# SCH_stm-mainboard_2026-06-05.net
KiCad netlist of a schematic drawn in EasyEDA
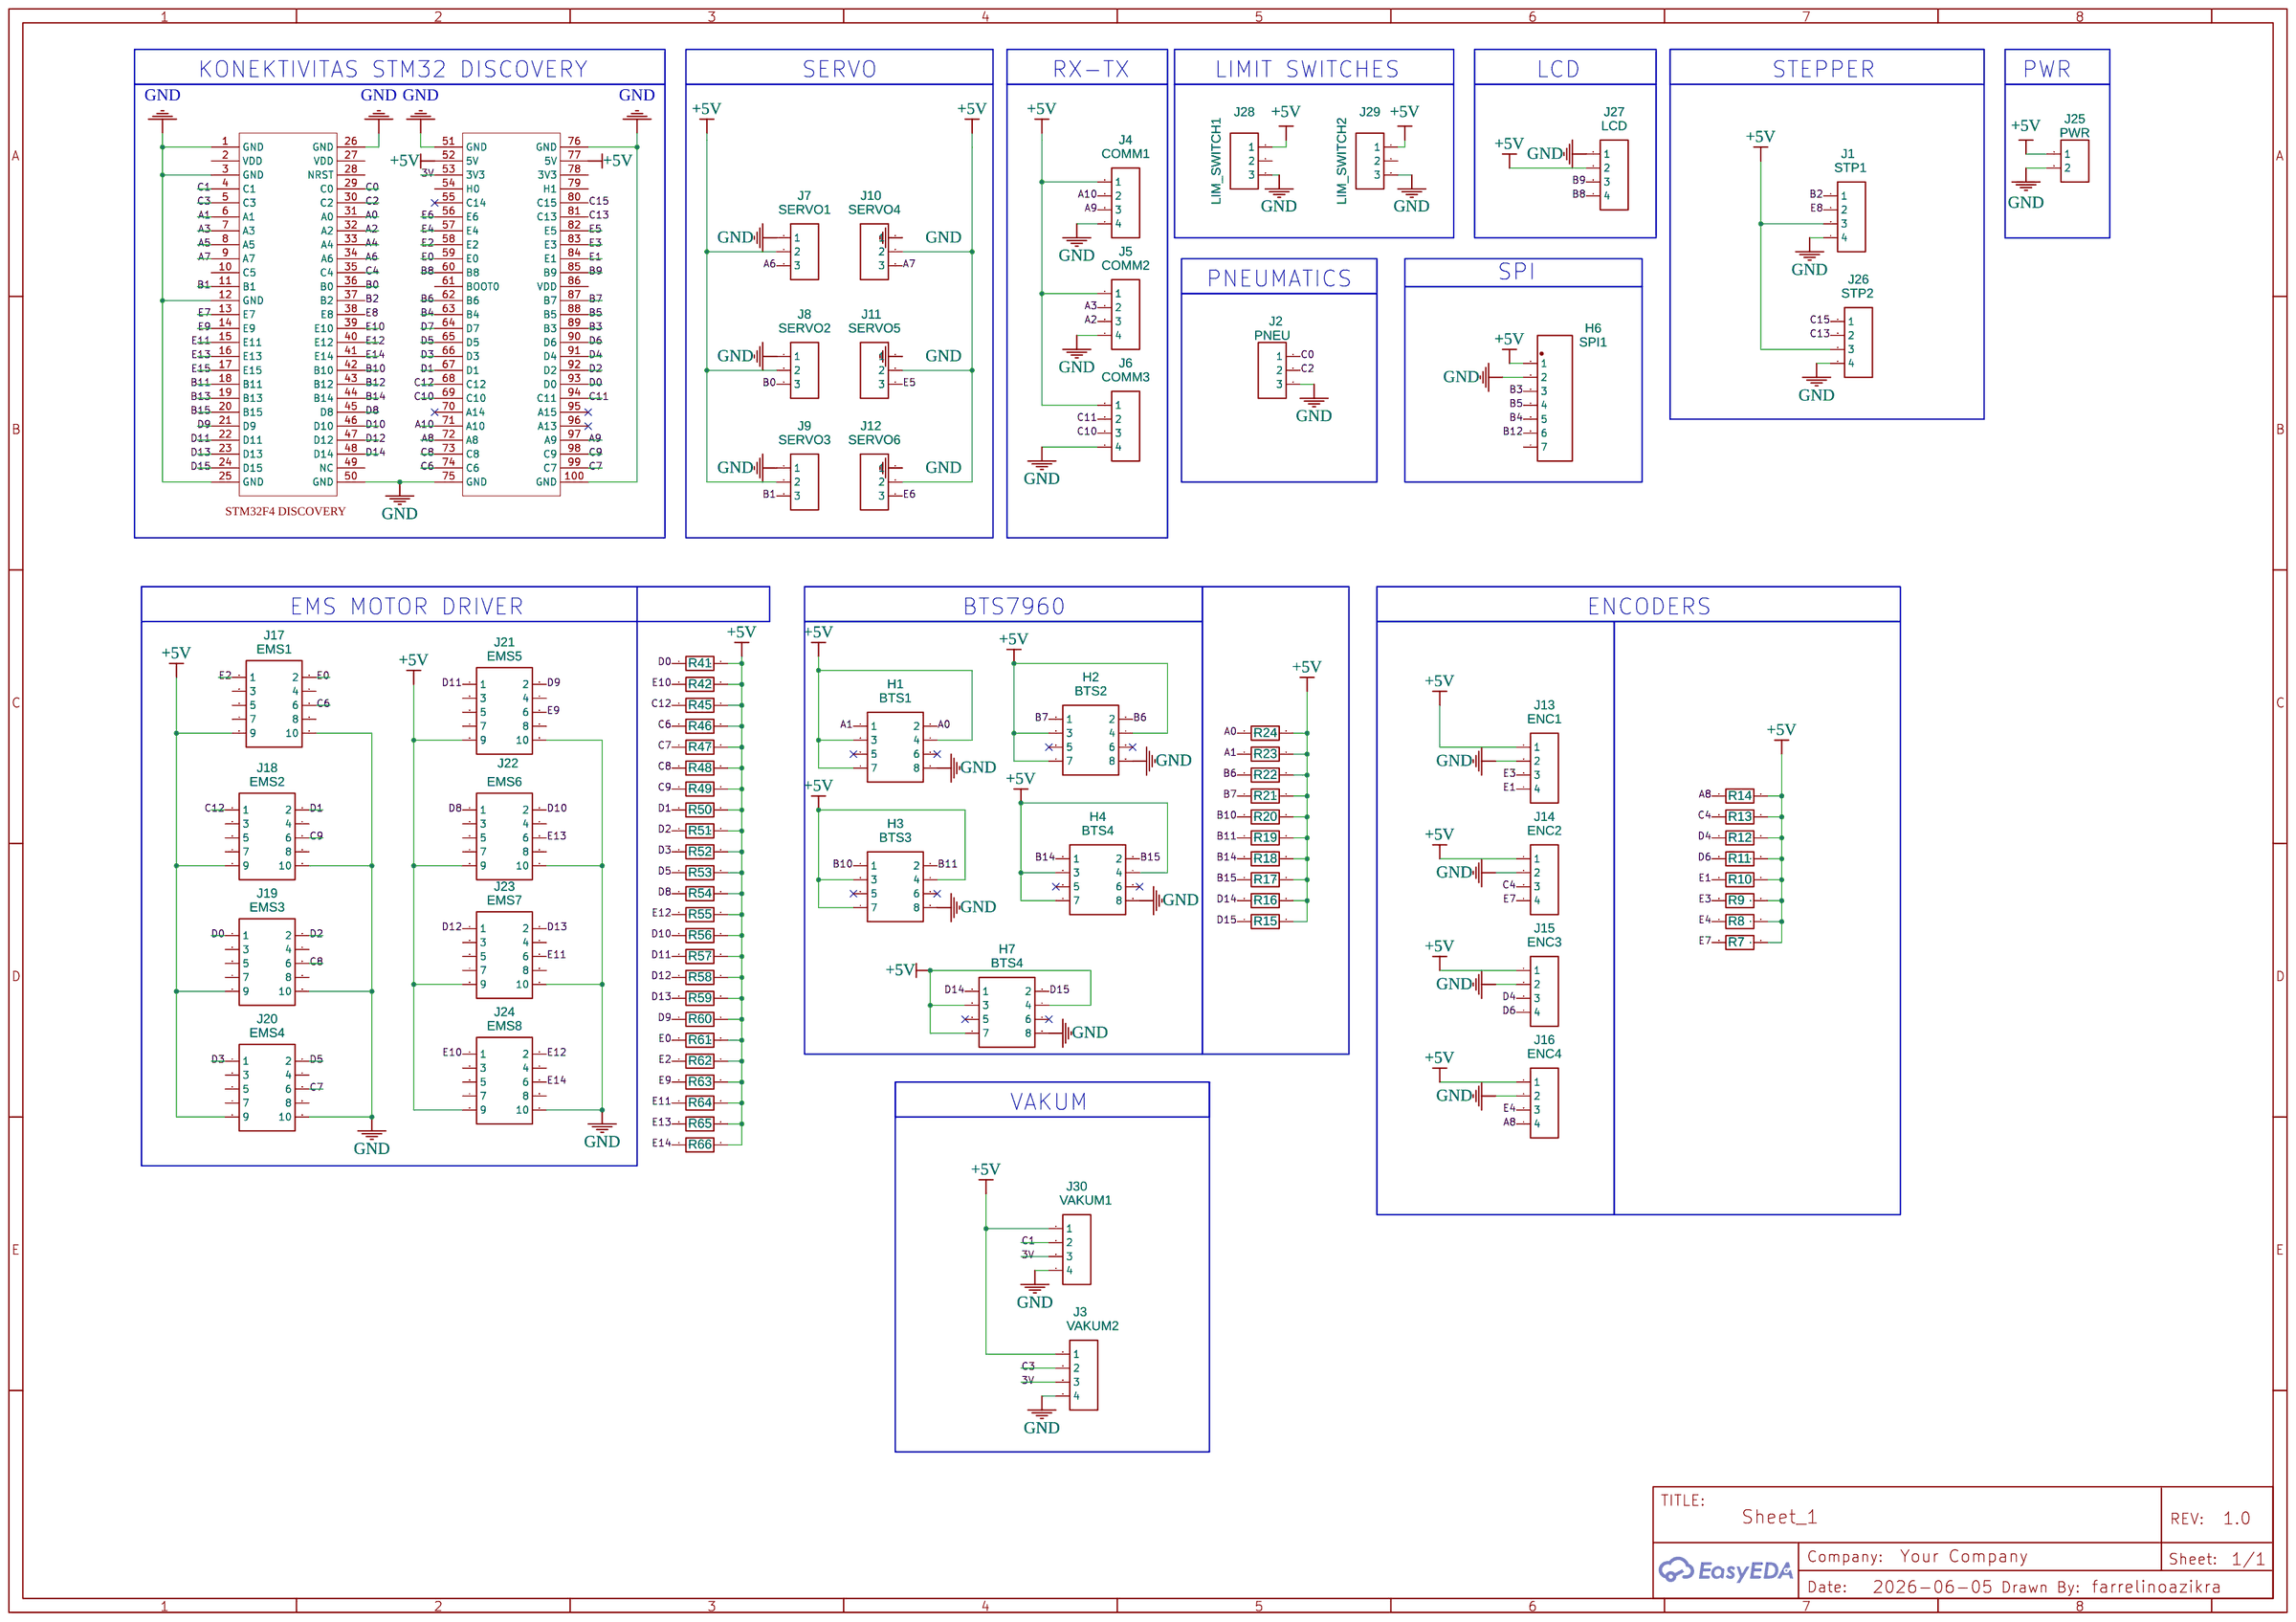
[diagram p0: schematic sheet]

(export (version "E")
  (design (tool "Eeschema 10.0.6"))
  (components
    (comp (ref "H1") (value "BTS1") (libsource (lib "") (part "HDR-F-2.54_2x4")))
    (comp (ref "H2") (value "BTS2") (libsource (lib "") (part "HDR-F-2.54_2x4")))
    (comp (ref "H3") (value "BTS3") (libsource (lib "") (part "HDR-F-2.54_2x4")))
    (comp (ref "H4") (value "BTS4") (libsource (lib "") (part "HDR-F-2.54_2x4")))
    (comp (ref "H6")
      (value "SPI1")
      (fields (field (name "Manufacturer Part") "210S-1*7P") (field (name "Manufacturer") "Ckmtw"))
      (libsource (lib "") (part "Header-Male-2.54_1x7"))
    )
    (comp (ref "H7") (value "BTS4") (libsource (lib "") (part "HDR-F-2.54_2x4")))
    (comp (ref "J1") (value "STP1") (libsource (lib "") (part "HDR-M-2.54_1x4")))
    (comp (ref "J2") (value "PNEU") (libsource (lib "") (part "HDR-M-2.54_1x3")))
    (comp (ref "J3") (value "VAKUM2") (libsource (lib "") (part "HDR-M-2.54_1x4")))
    (comp (ref "J4") (value "COMM1") (libsource (lib "") (part "HDR-M-2.54_1x4")))
    (comp (ref "J5") (value "COMM2") (libsource (lib "") (part "HDR-M-2.54_1x4")))
    (comp (ref "J6") (value "COMM3") (libsource (lib "") (part "HDR-M-2.54_1x4")))
    (comp (ref "J7") (value "SERVO1") (libsource (lib "") (part "HDR-M-2.54_1x3_1")))
    (comp (ref "J8") (value "SERVO2") (libsource (lib "") (part "HDR-M-2.54_1x3_1")))
    (comp (ref "J9") (value "SERVO3") (libsource (lib "") (part "HDR-M-2.54_1x3_1")))
    (comp (ref "J10") (value "SERVO4") (libsource (lib "") (part "HDR-M-2.54_1x3")))
    (comp (ref "J11") (value "SERVO5") (libsource (lib "") (part "HDR-M-2.54_1x3")))
    (comp (ref "J12") (value "SERVO6") (libsource (lib "") (part "HDR-M-2.54_1x3")))
    (comp (ref "J13") (value "ENC1") (libsource (lib "") (part "HDR-M-2.54_1x4")))
    (comp (ref "J14") (value "ENC2") (libsource (lib "") (part "HDR-M-2.54_1x4")))
    (comp (ref "J15") (value "ENC3") (libsource (lib "") (part "HDR-M-2.54_1x4")))
    (comp (ref "J16") (value "ENC4") (libsource (lib "") (part "HDR-M-2.54_1x4")))
    (comp (ref "J17") (value "EMS1") (libsource (lib "") (part "HDR-M-2.54_2x5")))
    (comp (ref "J18") (value "EMS2") (libsource (lib "") (part "HDR-M-2.54_2x5")))
    (comp (ref "J19") (value "EMS3") (libsource (lib "") (part "HDR-M-2.54_2x5")))
    (comp (ref "J20") (value "EMS4") (libsource (lib "") (part "HDR-M-2.54_2x5")))
    (comp (ref "J21") (value "EMS5") (libsource (lib "") (part "HDR-M-2.54_2x5")))
    (comp (ref "J22") (value "EMS6") (libsource (lib "") (part "HDR-M-2.54_2x5")))
    (comp (ref "J23") (value "EMS7") (libsource (lib "") (part "HDR-M-2.54_2x5")))
    (comp (ref "J24") (value "EMS8") (libsource (lib "") (part "HDR-M-2.54_2x5")))
    (comp (ref "J25") (value "PWR") (libsource (lib "") (part "HDR-M-2.54_1x2")))
    (comp (ref "J26") (value "STP2") (libsource (lib "") (part "HDR-M-2.54_1x4")))
    (comp (ref "J27") (value "LCD") (libsource (lib "") (part "HDR-M-2.54_1x4")))
    (comp (ref "J28") (value "LIM_SWITCH1") (libsource (lib "") (part "HDR-M-2.54_1x3")))
    (comp (ref "J29") (value "LIM_SWITCH2") (libsource (lib "") (part "HDR-M-2.54_1x3")))
    (comp (ref "J30") (value "VAKUM1") (libsource (lib "") (part "HDR-M-2.54_1x4")))
    (comp (ref "R7") (value "1k") (libsource (lib "") (part "R_1206_EU")))
    (comp (ref "R8") (value "1k") (libsource (lib "") (part "R_1206_EU")))
    (comp (ref "R9") (value "1k") (libsource (lib "") (part "R_1206_EU")))
    (comp (ref "R10") (value "1k") (libsource (lib "") (part "R_1206_EU")))
    (comp (ref "R11") (value "1k") (libsource (lib "") (part "R_1206_EU")))
    (comp (ref "R12") (value "1k") (libsource (lib "") (part "R_1206_EU")))
    (comp (ref "R13") (value "1k") (libsource (lib "") (part "R_1206_EU")))
    (comp (ref "R14") (value "1k") (libsource (lib "") (part "R_1206_EU")))
    (comp (ref "R15") (value "1k") (libsource (lib "") (part "R_1206_EU")))
    (comp (ref "R16") (value "1k") (libsource (lib "") (part "R_1206_EU")))
    (comp (ref "R17") (value "1k") (libsource (lib "") (part "R_1206_EU")))
    (comp (ref "R18") (value "1k") (libsource (lib "") (part "R_1206_EU")))
    (comp (ref "R19") (value "1k") (libsource (lib "") (part "R_1206_EU")))
    (comp (ref "R20") (value "1k") (libsource (lib "") (part "R_1206_EU")))
    (comp (ref "R21") (value "1k") (libsource (lib "") (part "R_1206_EU")))
    (comp (ref "R22") (value "1k") (libsource (lib "") (part "R_1206_EU")))
    (comp (ref "R23") (value "1k") (libsource (lib "") (part "R_1206_EU")))
    (comp (ref "R24") (value "1k") (libsource (lib "") (part "R_1206_EU")))
    (comp (ref "R41") (value "1k") (libsource (lib "") (part "R_1206_EU")))
    (comp (ref "R42") (value "1k") (libsource (lib "") (part "R_1206_EU")))
    (comp (ref "R45") (value "1k") (libsource (lib "") (part "R_1206_EU")))
    (comp (ref "R46") (value "1k") (libsource (lib "") (part "R_1206_EU")))
    (comp (ref "R47") (value "1k") (libsource (lib "") (part "R_1206_EU")))
    (comp (ref "R48") (value "1k") (libsource (lib "") (part "R_1206_EU")))
    (comp (ref "R49") (value "1k") (libsource (lib "") (part "R_1206_EU")))
    (comp (ref "R50") (value "1k") (libsource (lib "") (part "R_1206_EU")))
    (comp (ref "R51") (value "1k") (libsource (lib "") (part "R_1206_EU")))
    (comp (ref "R52") (value "1k") (libsource (lib "") (part "R_1206_EU")))
    (comp (ref "R53") (value "1k") (libsource (lib "") (part "R_1206_EU")))
    (comp (ref "R54") (value "1k") (libsource (lib "") (part "R_1206_EU")))
    (comp (ref "R55") (value "1k") (libsource (lib "") (part "R_1206_EU")))
    (comp (ref "R56") (value "1k") (libsource (lib "") (part "R_1206_EU")))
    (comp (ref "R57") (value "1k") (libsource (lib "") (part "R_1206_EU")))
    (comp (ref "R58") (value "1k") (libsource (lib "") (part "R_1206_EU")))
    (comp (ref "R59") (value "1k") (libsource (lib "") (part "R_1206_EU")))
    (comp (ref "R60") (value "1k") (libsource (lib "") (part "R_1206_EU")))
    (comp (ref "R61") (value "1k") (libsource (lib "") (part "R_1206_EU")))
    (comp (ref "R62") (value "1k") (libsource (lib "") (part "R_1206_EU")))
    (comp (ref "R63") (value "1k") (libsource (lib "") (part "R_1206_EU")))
    (comp (ref "R64") (value "1k") (libsource (lib "") (part "R_1206_EU")))
    (comp (ref "R65") (value "1k") (libsource (lib "") (part "R_1206_EU")))
    (comp (ref "R66") (value "1k") (libsource (lib "") (part "R_1206_EU")))
    (comp (ref "STM32F1DISCOVERY")
      (value "STM32F4 Discovery")
      (libsource (lib "") (part "Unknown_145_-1060"))
    )
  )
  (nets
    (net (code "1") (name "+5V") (class "Default")
      (node (ref "H1") (pin "3") (pinfunction "3_3") (pintype "unspecified"))
      (node (ref "H1") (pin "4") (pinfunction "4_4") (pintype "unspecified"))
      (node (ref "H1") (pin "7") (pinfunction "7_7") (pintype "unspecified"))
      (node (ref "H2") (pin "3") (pinfunction "3_3") (pintype "unspecified"))
      (node (ref "H2") (pin "4") (pinfunction "4_4") (pintype "unspecified"))
      (node (ref "H2") (pin "7") (pinfunction "7_7") (pintype "unspecified"))
      (node (ref "H3") (pin "3") (pinfunction "3_3") (pintype "unspecified"))
      (node (ref "H3") (pin "4") (pinfunction "4_4") (pintype "unspecified"))
      (node (ref "H3") (pin "7") (pinfunction "7_7") (pintype "unspecified"))
      (node (ref "H4") (pin "3") (pinfunction "3_3") (pintype "unspecified"))
      (node (ref "H4") (pin "4") (pinfunction "4_4") (pintype "unspecified"))
      (node (ref "H4") (pin "7") (pinfunction "7_7") (pintype "unspecified"))
      (node (ref "H6") (pin "1") (pinfunction "1_1") (pintype "unspecified"))
      (node (ref "H7") (pin "3") (pinfunction "3_3") (pintype "unspecified"))
      (node (ref "H7") (pin "4") (pinfunction "4_4") (pintype "unspecified"))
      (node (ref "H7") (pin "7") (pinfunction "7_7") (pintype "unspecified"))
      (node (ref "J1") (pin "3") (pinfunction "3_3") (pintype "unspecified"))
      (node (ref "J10") (pin "2") (pinfunction "2_2") (pintype "input"))
      (node (ref "J11") (pin "2") (pinfunction "2_2") (pintype "input"))
      (node (ref "J12") (pin "2") (pinfunction "2_2") (pintype "input"))
      (node (ref "J13") (pin "1") (pinfunction "1_1") (pintype "unspecified"))
      (node (ref "J14") (pin "1") (pinfunction "1_1") (pintype "unspecified"))
      (node (ref "J15") (pin "1") (pinfunction "1_1") (pintype "unspecified"))
      (node (ref "J16") (pin "1") (pinfunction "1_1") (pintype "unspecified"))
      (node (ref "J17") (pin "9") (pinfunction "9_9") (pintype "unspecified"))
      (node (ref "J18") (pin "9") (pinfunction "9_9") (pintype "unspecified"))
      (node (ref "J19") (pin "9") (pinfunction "9_9") (pintype "unspecified"))
      (node (ref "J20") (pin "9") (pinfunction "9_9") (pintype "unspecified"))
      (node (ref "J21") (pin "9") (pinfunction "9_9") (pintype "unspecified"))
      (node (ref "J22") (pin "9") (pinfunction "9_9") (pintype "unspecified"))
      (node (ref "J23") (pin "9") (pinfunction "9_9") (pintype "unspecified"))
      (node (ref "J24") (pin "9") (pinfunction "9_9") (pintype "unspecified"))
      (node (ref "J25") (pin "1") (pinfunction "1_1") (pintype "unspecified"))
      (node (ref "J26") (pin "3") (pinfunction "3_3") (pintype "unspecified"))
      (node (ref "J27") (pin "2") (pinfunction "2_2") (pintype "unspecified"))
      (node (ref "J28") (pin "1") (pinfunction "1_1") (pintype "input"))
      (node (ref "J29") (pin "1") (pinfunction "1_1") (pintype "input"))
      (node (ref "J3") (pin "1") (pinfunction "1_1") (pintype "unspecified"))
      (node (ref "J30") (pin "1") (pinfunction "1_1") (pintype "unspecified"))
      (node (ref "J4") (pin "1") (pinfunction "1_1") (pintype "unspecified"))
      (node (ref "J5") (pin "1") (pinfunction "1_1") (pintype "unspecified"))
      (node (ref "J6") (pin "1") (pinfunction "1_1") (pintype "unspecified"))
      (node (ref "J7") (pin "2") (pinfunction "2_2") (pintype "input"))
      (node (ref "J8") (pin "2") (pinfunction "2_2") (pintype "input"))
      (node (ref "J9") (pin "2") (pinfunction "2_2") (pintype "input"))
      (node (ref "R10") (pin "2") (pinfunction "2_2") (pintype "unspecified"))
      (node (ref "R11") (pin "2") (pinfunction "2_2") (pintype "unspecified"))
      (node (ref "R12") (pin "2") (pinfunction "2_2") (pintype "unspecified"))
      (node (ref "R13") (pin "2") (pinfunction "2_2") (pintype "unspecified"))
      (node (ref "R14") (pin "2") (pinfunction "2_2") (pintype "unspecified"))
      (node (ref "R15") (pin "2") (pinfunction "2_2") (pintype "unspecified"))
      (node (ref "R16") (pin "2") (pinfunction "2_2") (pintype "unspecified"))
      (node (ref "R17") (pin "2") (pinfunction "2_2") (pintype "unspecified"))
      (node (ref "R18") (pin "2") (pinfunction "2_2") (pintype "unspecified"))
      (node (ref "R19") (pin "2") (pinfunction "2_2") (pintype "unspecified"))
      (node (ref "R20") (pin "2") (pinfunction "2_2") (pintype "unspecified"))
      (node (ref "R21") (pin "2") (pinfunction "2_2") (pintype "unspecified"))
      (node (ref "R22") (pin "2") (pinfunction "2_2") (pintype "unspecified"))
      (node (ref "R23") (pin "2") (pinfunction "2_2") (pintype "unspecified"))
      (node (ref "R24") (pin "2") (pinfunction "2_2") (pintype "unspecified"))
      (node (ref "R41") (pin "2") (pinfunction "2_2") (pintype "unspecified"))
      (node (ref "R42") (pin "2") (pinfunction "2_2") (pintype "unspecified"))
      (node (ref "R45") (pin "2") (pinfunction "2_2") (pintype "unspecified"))
      (node (ref "R46") (pin "2") (pinfunction "2_2") (pintype "unspecified"))
      (node (ref "R47") (pin "2") (pinfunction "2_2") (pintype "unspecified"))
      (node (ref "R48") (pin "2") (pinfunction "2_2") (pintype "unspecified"))
      (node (ref "R49") (pin "2") (pinfunction "2_2") (pintype "unspecified"))
      (node (ref "R50") (pin "2") (pinfunction "2_2") (pintype "unspecified"))
      (node (ref "R51") (pin "2") (pinfunction "2_2") (pintype "unspecified"))
      (node (ref "R52") (pin "2") (pinfunction "2_2") (pintype "unspecified"))
      (node (ref "R53") (pin "2") (pinfunction "2_2") (pintype "unspecified"))
      (node (ref "R54") (pin "2") (pinfunction "2_2") (pintype "unspecified"))
      (node (ref "R55") (pin "2") (pinfunction "2_2") (pintype "unspecified"))
      (node (ref "R56") (pin "2") (pinfunction "2_2") (pintype "unspecified"))
      (node (ref "R57") (pin "2") (pinfunction "2_2") (pintype "unspecified"))
      (node (ref "R58") (pin "2") (pinfunction "2_2") (pintype "unspecified"))
      (node (ref "R59") (pin "2") (pinfunction "2_2") (pintype "unspecified"))
      (node (ref "R60") (pin "2") (pinfunction "2_2") (pintype "unspecified"))
      (node (ref "R61") (pin "2") (pinfunction "2_2") (pintype "unspecified"))
      (node (ref "R62") (pin "2") (pinfunction "2_2") (pintype "unspecified"))
      (node (ref "R63") (pin "2") (pinfunction "2_2") (pintype "unspecified"))
      (node (ref "R64") (pin "2") (pinfunction "2_2") (pintype "unspecified"))
      (node (ref "R65") (pin "2") (pinfunction "2_2") (pintype "unspecified"))
      (node (ref "R66") (pin "2") (pinfunction "2_2") (pintype "unspecified"))
      (node (ref "R7") (pin "2") (pinfunction "2_2") (pintype "unspecified"))
      (node (ref "R8") (pin "2") (pinfunction "2_2") (pintype "unspecified"))
      (node (ref "R9") (pin "2") (pinfunction "2_2") (pintype "unspecified"))
      (node (ref "STM32F1DISCOVERY") (pin "52") (pinfunction "5V_52") (pintype "passive"))
      (node (ref "STM32F1DISCOVERY") (pin "77") (pinfunction "5V_77") (pintype "passive"))
    )
    (net (code "2") (name "/3V") (class "Default")
      (node (ref "J3") (pin "3") (pinfunction "3_3") (pintype "unspecified"))
      (node (ref "J30") (pin "3") (pinfunction "3_3") (pintype "unspecified"))
      (node (ref "STM32F1DISCOVERY") (pin "53") (pinfunction "3V3_53") (pintype "passive"))
    )
    (net (code "3") (name "/A0") (class "Default")
      (node (ref "H1") (pin "2") (pinfunction "2_2") (pintype "unspecified"))
      (node (ref "R24") (pin "1") (pinfunction "1_1") (pintype "unspecified"))
      (node (ref "STM32F1DISCOVERY") (pin "31") (pinfunction "A0_31") (pintype "bidirectional"))
    )
    (net (code "4") (name "/A1") (class "Default")
      (node (ref "H1") (pin "1") (pinfunction "1_1") (pintype "unspecified"))
      (node (ref "R23") (pin "1") (pinfunction "1_1") (pintype "unspecified"))
      (node (ref "STM32F1DISCOVERY") (pin "6") (pinfunction "A1_6") (pintype "bidirectional"))
    )
    (net (code "5") (name "/A2") (class "Default")
      (node (ref "J5") (pin "3") (pinfunction "3_3") (pintype "unspecified"))
      (node (ref "STM32F1DISCOVERY") (pin "32") (pinfunction "A2_32") (pintype "bidirectional"))
    )
    (net (code "6") (name "/A3") (class "Default")
      (node (ref "J5") (pin "2") (pinfunction "2_2") (pintype "unspecified"))
      (node (ref "STM32F1DISCOVERY") (pin "7") (pinfunction "A3_7") (pintype "bidirectional"))
    )
    (net (code "7") (name "/A4") (class "Default")
      (node (ref "STM32F1DISCOVERY") (pin "33") (pinfunction "A4_33") (pintype "bidirectional"))
    )
    (net (code "8") (name "/A5") (class "Default")
      (node (ref "STM32F1DISCOVERY") (pin "8") (pinfunction "A5_8") (pintype "bidirectional"))
    )
    (net (code "9") (name "/A6") (class "Default")
      (node (ref "J7") (pin "3") (pinfunction "3_3") (pintype "input"))
      (node (ref "STM32F1DISCOVERY") (pin "34") (pinfunction "A6_34") (pintype "bidirectional"))
    )
    (net (code "10") (name "/A7") (class "Default")
      (node (ref "J10") (pin "3") (pinfunction "3_3") (pintype "input"))
      (node (ref "STM32F1DISCOVERY") (pin "9") (pinfunction "A7_9") (pintype "bidirectional"))
    )
    (net (code "11") (name "/A8") (class "Default")
      (node (ref "J16") (pin "4") (pinfunction "4_4") (pintype "unspecified"))
      (node (ref "R14") (pin "1") (pinfunction "1_1") (pintype "unspecified"))
      (node (ref "STM32F1DISCOVERY") (pin "72") (pinfunction "A8_72") (pintype "bidirectional"))
    )
    (net (code "12") (name "/A9") (class "Default")
      (node (ref "J4") (pin "3") (pinfunction "3_3") (pintype "unspecified"))
      (node (ref "STM32F1DISCOVERY") (pin "97") (pinfunction "A9_97") (pintype "bidirectional"))
    )
    (net (code "13") (name "/A10") (class "Default")
      (node (ref "J4") (pin "2") (pinfunction "2_2") (pintype "unspecified"))
      (node (ref "STM32F1DISCOVERY") (pin "71") (pinfunction "A10_71") (pintype "bidirectional"))
    )
    (net (code "14") (name "/B0") (class "Default")
      (node (ref "J8") (pin "3") (pinfunction "3_3") (pintype "input"))
      (node (ref "STM32F1DISCOVERY") (pin "36") (pinfunction "B0_36") (pintype "bidirectional"))
    )
    (net (code "15") (name "/B1") (class "Default")
      (node (ref "J9") (pin "3") (pinfunction "3_3") (pintype "input"))
      (node (ref "STM32F1DISCOVERY") (pin "11") (pinfunction "B1_11") (pintype "bidirectional"))
    )
    (net (code "16") (name "/B2") (class "Default")
      (node (ref "J1") (pin "1") (pinfunction "1_1") (pintype "unspecified"))
      (node (ref "STM32F1DISCOVERY") (pin "37") (pinfunction "B2_37") (pintype "bidirectional"))
    )
    (net (code "17") (name "/B3") (class "Default")
      (node (ref "H6") (pin "3") (pinfunction "3_3") (pintype "unspecified"))
      (node (ref "STM32F1DISCOVERY") (pin "89") (pinfunction "B3_89") (pintype "bidirectional"))
    )
    (net (code "18") (name "/B4") (class "Default")
      (node (ref "H6") (pin "5") (pinfunction "5_5") (pintype "unspecified"))
      (node (ref "STM32F1DISCOVERY") (pin "63") (pinfunction "B4_63") (pintype "bidirectional"))
    )
    (net (code "19") (name "/B5") (class "Default")
      (node (ref "H6") (pin "4") (pinfunction "4_4") (pintype "unspecified"))
      (node (ref "STM32F1DISCOVERY") (pin "88") (pinfunction "B5_88") (pintype "bidirectional"))
    )
    (net (code "20") (name "/B6") (class "Default")
      (node (ref "H2") (pin "2") (pinfunction "2_2") (pintype "unspecified"))
      (node (ref "R22") (pin "1") (pinfunction "1_1") (pintype "unspecified"))
      (node (ref "STM32F1DISCOVERY") (pin "62") (pinfunction "B6_62") (pintype "bidirectional"))
    )
    (net (code "21") (name "/B7") (class "Default")
      (node (ref "H2") (pin "1") (pinfunction "1_1") (pintype "unspecified"))
      (node (ref "R21") (pin "1") (pinfunction "1_1") (pintype "unspecified"))
      (node (ref "STM32F1DISCOVERY") (pin "87") (pinfunction "B7_87") (pintype "bidirectional"))
    )
    (net (code "22") (name "/B8") (class "Default")
      (node (ref "J27") (pin "4") (pinfunction "4_4") (pintype "unspecified"))
      (node (ref "STM32F1DISCOVERY") (pin "60") (pinfunction "B8_60") (pintype "bidirectional"))
    )
    (net (code "23") (name "/B9") (class "Default")
      (node (ref "J27") (pin "3") (pinfunction "3_3") (pintype "unspecified"))
      (node (ref "STM32F1DISCOVERY") (pin "85") (pinfunction "B9_85") (pintype "bidirectional"))
    )
    (net (code "24") (name "/B10") (class "Default")
      (node (ref "H3") (pin "1") (pinfunction "1_1") (pintype "unspecified"))
      (node (ref "R20") (pin "1") (pinfunction "1_1") (pintype "unspecified"))
      (node (ref "STM32F1DISCOVERY") (pin "42") (pinfunction "B10_42") (pintype "bidirectional"))
    )
    (net (code "25") (name "/B11") (class "Default")
      (node (ref "H3") (pin "2") (pinfunction "2_2") (pintype "unspecified"))
      (node (ref "R19") (pin "1") (pinfunction "1_1") (pintype "unspecified"))
      (node (ref "STM32F1DISCOVERY") (pin "18") (pinfunction "B11_18") (pintype "bidirectional"))
    )
    (net (code "26") (name "/B12") (class "Default")
      (node (ref "H6") (pin "6") (pinfunction "6_6") (pintype "unspecified"))
      (node (ref "STM32F1DISCOVERY") (pin "43") (pinfunction "B12_43") (pintype "bidirectional"))
    )
    (net (code "27") (name "/B13") (class "Default")
      (node (ref "STM32F1DISCOVERY") (pin "19") (pinfunction "B13_19") (pintype "bidirectional"))
    )
    (net (code "28") (name "/B14") (class "Default")
      (node (ref "H4") (pin "1") (pinfunction "1_1") (pintype "unspecified"))
      (node (ref "R18") (pin "1") (pinfunction "1_1") (pintype "unspecified"))
      (node (ref "STM32F1DISCOVERY") (pin "44") (pinfunction "B14_44") (pintype "bidirectional"))
    )
    (net (code "29") (name "/B15") (class "Default")
      (node (ref "H4") (pin "2") (pinfunction "2_2") (pintype "unspecified"))
      (node (ref "R17") (pin "1") (pinfunction "1_1") (pintype "unspecified"))
      (node (ref "STM32F1DISCOVERY") (pin "20") (pinfunction "B15_20") (pintype "bidirectional"))
    )
    (net (code "30") (name "/C0") (class "Default")
      (node (ref "J2") (pin "1") (pinfunction "1_1") (pintype "input"))
      (node (ref "STM32F1DISCOVERY") (pin "29") (pinfunction "C0_29") (pintype "bidirectional"))
    )
    (net (code "31") (name "/C1") (class "Default")
      (node (ref "J30") (pin "2") (pinfunction "2_2") (pintype "unspecified"))
      (node (ref "STM32F1DISCOVERY") (pin "4") (pinfunction "C1_4") (pintype "bidirectional"))
    )
    (net (code "32") (name "/C2") (class "Default")
      (node (ref "J2") (pin "2") (pinfunction "2_2") (pintype "input"))
      (node (ref "STM32F1DISCOVERY") (pin "30") (pinfunction "C2_30") (pintype "bidirectional"))
    )
    (net (code "33") (name "/C3") (class "Default")
      (node (ref "J3") (pin "2") (pinfunction "2_2") (pintype "unspecified"))
      (node (ref "STM32F1DISCOVERY") (pin "5") (pinfunction "C3_5") (pintype "bidirectional"))
    )
    (net (code "34") (name "/C4") (class "Default")
      (node (ref "J14") (pin "3") (pinfunction "3_3") (pintype "unspecified"))
      (node (ref "R13") (pin "1") (pinfunction "1_1") (pintype "unspecified"))
      (node (ref "STM32F1DISCOVERY") (pin "35") (pinfunction "C4_35") (pintype "bidirectional"))
    )
    (net (code "35") (name "/C6") (class "Default")
      (node (ref "J17") (pin "6") (pinfunction "6_6") (pintype "unspecified"))
      (node (ref "R46") (pin "1") (pinfunction "1_1") (pintype "unspecified"))
      (node (ref "STM32F1DISCOVERY") (pin "74") (pinfunction "C6_74") (pintype "bidirectional"))
    )
    (net (code "36") (name "/C7") (class "Default")
      (node (ref "J20") (pin "6") (pinfunction "6_6") (pintype "unspecified"))
      (node (ref "R47") (pin "1") (pinfunction "1_1") (pintype "unspecified"))
      (node (ref "STM32F1DISCOVERY") (pin "99") (pinfunction "C7_99") (pintype "bidirectional"))
    )
    (net (code "37") (name "/C8") (class "Default")
      (node (ref "J19") (pin "6") (pinfunction "6_6") (pintype "unspecified"))
      (node (ref "R48") (pin "1") (pinfunction "1_1") (pintype "unspecified"))
      (node (ref "STM32F1DISCOVERY") (pin "73") (pinfunction "C8_73") (pintype "bidirectional"))
    )
    (net (code "38") (name "/C9") (class "Default")
      (node (ref "J18") (pin "6") (pinfunction "6_6") (pintype "unspecified"))
      (node (ref "R49") (pin "1") (pinfunction "1_1") (pintype "unspecified"))
      (node (ref "STM32F1DISCOVERY") (pin "98") (pinfunction "C9_98") (pintype "bidirectional"))
    )
    (net (code "39") (name "/C10") (class "Default")
      (node (ref "J6") (pin "3") (pinfunction "3_3") (pintype "unspecified"))
      (node (ref "STM32F1DISCOVERY") (pin "69") (pinfunction "C10_69") (pintype "bidirectional"))
    )
    (net (code "40") (name "/C11") (class "Default")
      (node (ref "J6") (pin "2") (pinfunction "2_2") (pintype "unspecified"))
      (node (ref "STM32F1DISCOVERY") (pin "94") (pinfunction "C11_94") (pintype "bidirectional"))
    )
    (net (code "41") (name "/C12") (class "Default")
      (node (ref "J18") (pin "1") (pinfunction "1_1") (pintype "unspecified"))
      (node (ref "R45") (pin "1") (pinfunction "1_1") (pintype "unspecified"))
      (node (ref "STM32F1DISCOVERY") (pin "68") (pinfunction "C12_68") (pintype "bidirectional"))
    )
    (net (code "42") (name "/C13") (class "Default")
      (node (ref "J26") (pin "2") (pinfunction "2_2") (pintype "unspecified"))
      (node (ref "STM32F1DISCOVERY") (pin "81") (pinfunction "C13_81") (pintype "bidirectional"))
    )
    (net (code "43") (name "/C15") (class "Default")
      (node (ref "J26") (pin "1") (pinfunction "1_1") (pintype "unspecified"))
      (node (ref "STM32F1DISCOVERY") (pin "80") (pinfunction "C15_80") (pintype "bidirectional"))
    )
    (net (code "44") (name "/D0") (class "Default")
      (node (ref "J19") (pin "1") (pinfunction "1_1") (pintype "unspecified"))
      (node (ref "R41") (pin "1") (pinfunction "1_1") (pintype "unspecified"))
      (node (ref "STM32F1DISCOVERY") (pin "93") (pinfunction "D0_93") (pintype "bidirectional"))
    )
    (net (code "45") (name "/D1") (class "Default")
      (node (ref "J18") (pin "2") (pinfunction "2_2") (pintype "unspecified"))
      (node (ref "R50") (pin "1") (pinfunction "1_1") (pintype "unspecified"))
      (node (ref "STM32F1DISCOVERY") (pin "67") (pinfunction "D1_67") (pintype "bidirectional"))
    )
    (net (code "46") (name "/D2") (class "Default")
      (node (ref "J19") (pin "2") (pinfunction "2_2") (pintype "unspecified"))
      (node (ref "R51") (pin "1") (pinfunction "1_1") (pintype "unspecified"))
      (node (ref "STM32F1DISCOVERY") (pin "92") (pinfunction "D2_92") (pintype "bidirectional"))
    )
    (net (code "47") (name "/D3") (class "Default")
      (node (ref "J20") (pin "1") (pinfunction "1_1") (pintype "unspecified"))
      (node (ref "R52") (pin "1") (pinfunction "1_1") (pintype "unspecified"))
      (node (ref "STM32F1DISCOVERY") (pin "66") (pinfunction "D3_66") (pintype "bidirectional"))
    )
    (net (code "48") (name "/D4") (class "Default")
      (node (ref "J15") (pin "3") (pinfunction "3_3") (pintype "unspecified"))
      (node (ref "R12") (pin "1") (pinfunction "1_1") (pintype "unspecified"))
      (node (ref "STM32F1DISCOVERY") (pin "91") (pinfunction "D4_91") (pintype "bidirectional"))
    )
    (net (code "49") (name "/D5") (class "Default")
      (node (ref "J20") (pin "2") (pinfunction "2_2") (pintype "unspecified"))
      (node (ref "R53") (pin "1") (pinfunction "1_1") (pintype "unspecified"))
      (node (ref "STM32F1DISCOVERY") (pin "65") (pinfunction "D5_65") (pintype "bidirectional"))
    )
    (net (code "50") (name "/D6") (class "Default")
      (node (ref "J15") (pin "4") (pinfunction "4_4") (pintype "unspecified"))
      (node (ref "R11") (pin "1") (pinfunction "1_1") (pintype "unspecified"))
      (node (ref "STM32F1DISCOVERY") (pin "90") (pinfunction "D6_90") (pintype "bidirectional"))
    )
    (net (code "51") (name "/D7") (class "Default")
      (node (ref "STM32F1DISCOVERY") (pin "64") (pinfunction "D7_64") (pintype "bidirectional"))
    )
    (net (code "52") (name "/D8") (class "Default")
      (node (ref "J22") (pin "1") (pinfunction "1_1") (pintype "unspecified"))
      (node (ref "R54") (pin "1") (pinfunction "1_1") (pintype "unspecified"))
      (node (ref "STM32F1DISCOVERY") (pin "45") (pinfunction "D8_45") (pintype "bidirectional"))
    )
    (net (code "53") (name "/D9") (class "Default")
      (node (ref "J21") (pin "2") (pinfunction "2_2") (pintype "unspecified"))
      (node (ref "R60") (pin "1") (pinfunction "1_1") (pintype "unspecified"))
      (node (ref "STM32F1DISCOVERY") (pin "21") (pinfunction "D9_21") (pintype "bidirectional"))
    )
    (net (code "54") (name "/D10") (class "Default")
      (node (ref "J22") (pin "2") (pinfunction "2_2") (pintype "unspecified"))
      (node (ref "R56") (pin "1") (pinfunction "1_1") (pintype "unspecified"))
      (node (ref "STM32F1DISCOVERY") (pin "46") (pinfunction "D10_46") (pintype "bidirectional"))
    )
    (net (code "55") (name "/D11") (class "Default")
      (node (ref "J21") (pin "1") (pinfunction "1_1") (pintype "unspecified"))
      (node (ref "R57") (pin "1") (pinfunction "1_1") (pintype "unspecified"))
      (node (ref "STM32F1DISCOVERY") (pin "22") (pinfunction "D11_22") (pintype "bidirectional"))
    )
    (net (code "56") (name "/D12") (class "Default")
      (node (ref "J23") (pin "1") (pinfunction "1_1") (pintype "unspecified"))
      (node (ref "R58") (pin "1") (pinfunction "1_1") (pintype "unspecified"))
      (node (ref "STM32F1DISCOVERY") (pin "47") (pinfunction "D12_47") (pintype "bidirectional"))
    )
    (net (code "57") (name "/D13") (class "Default")
      (node (ref "J23") (pin "2") (pinfunction "2_2") (pintype "unspecified"))
      (node (ref "R59") (pin "1") (pinfunction "1_1") (pintype "unspecified"))
      (node (ref "STM32F1DISCOVERY") (pin "23") (pinfunction "D13_23") (pintype "bidirectional"))
    )
    (net (code "58") (name "/D14") (class "Default")
      (node (ref "H7") (pin "1") (pinfunction "1_1") (pintype "unspecified"))
      (node (ref "R16") (pin "1") (pinfunction "1_1") (pintype "unspecified"))
      (node (ref "STM32F1DISCOVERY") (pin "48") (pinfunction "D14_48") (pintype "bidirectional"))
    )
    (net (code "59") (name "/D15") (class "Default")
      (node (ref "H7") (pin "2") (pinfunction "2_2") (pintype "unspecified"))
      (node (ref "R15") (pin "1") (pinfunction "1_1") (pintype "unspecified"))
      (node (ref "STM32F1DISCOVERY") (pin "24") (pinfunction "D15_24") (pintype "bidirectional"))
    )
    (net (code "60") (name "/E0") (class "Default")
      (node (ref "J17") (pin "2") (pinfunction "2_2") (pintype "unspecified"))
      (node (ref "R61") (pin "1") (pinfunction "1_1") (pintype "unspecified"))
      (node (ref "STM32F1DISCOVERY") (pin "59") (pinfunction "E0_59") (pintype "bidirectional"))
    )
    (net (code "61") (name "/E1") (class "Default")
      (node (ref "J13") (pin "4") (pinfunction "4_4") (pintype "unspecified"))
      (node (ref "R10") (pin "1") (pinfunction "1_1") (pintype "unspecified"))
      (node (ref "STM32F1DISCOVERY") (pin "84") (pinfunction "E1_84") (pintype "bidirectional"))
    )
    (net (code "62") (name "/E2") (class "Default")
      (node (ref "J17") (pin "1") (pinfunction "1_1") (pintype "unspecified"))
      (node (ref "R62") (pin "1") (pinfunction "1_1") (pintype "unspecified"))
      (node (ref "STM32F1DISCOVERY") (pin "58") (pinfunction "E2_58") (pintype "bidirectional"))
    )
    (net (code "63") (name "/E3") (class "Default")
      (node (ref "J13") (pin "3") (pinfunction "3_3") (pintype "unspecified"))
      (node (ref "R9") (pin "1") (pinfunction "1_1") (pintype "unspecified"))
      (node (ref "STM32F1DISCOVERY") (pin "83") (pinfunction "E3_83") (pintype "bidirectional"))
    )
    (net (code "64") (name "/E4") (class "Default")
      (node (ref "J16") (pin "3") (pinfunction "3_3") (pintype "unspecified"))
      (node (ref "R8") (pin "1") (pinfunction "1_1") (pintype "unspecified"))
      (node (ref "STM32F1DISCOVERY") (pin "57") (pinfunction "E4_57") (pintype "bidirectional"))
    )
    (net (code "65") (name "/E5") (class "Default")
      (node (ref "J11") (pin "3") (pinfunction "3_3") (pintype "input"))
      (node (ref "STM32F1DISCOVERY") (pin "82") (pinfunction "E5_82") (pintype "bidirectional"))
    )
    (net (code "66") (name "/E6") (class "Default")
      (node (ref "J12") (pin "3") (pinfunction "3_3") (pintype "input"))
      (node (ref "STM32F1DISCOVERY") (pin "56") (pinfunction "E6_56") (pintype "bidirectional"))
    )
    (net (code "67") (name "/E7") (class "Default")
      (node (ref "J14") (pin "4") (pinfunction "4_4") (pintype "unspecified"))
      (node (ref "R7") (pin "1") (pinfunction "1_1") (pintype "unspecified"))
      (node (ref "STM32F1DISCOVERY") (pin "13") (pinfunction "E7_13") (pintype "bidirectional"))
    )
    (net (code "68") (name "/E8") (class "Default")
      (node (ref "J1") (pin "2") (pinfunction "2_2") (pintype "unspecified"))
      (node (ref "STM32F1DISCOVERY") (pin "38") (pinfunction "E8_38") (pintype "bidirectional"))
    )
    (net (code "69") (name "/E9") (class "Default")
      (node (ref "J21") (pin "6") (pinfunction "6_6") (pintype "unspecified"))
      (node (ref "R63") (pin "1") (pinfunction "1_1") (pintype "unspecified"))
      (node (ref "STM32F1DISCOVERY") (pin "14") (pinfunction "E9_14") (pintype "bidirectional"))
    )
    (net (code "70") (name "/E10") (class "Default")
      (node (ref "J24") (pin "1") (pinfunction "1_1") (pintype "unspecified"))
      (node (ref "R42") (pin "1") (pinfunction "1_1") (pintype "unspecified"))
      (node (ref "STM32F1DISCOVERY") (pin "39") (pinfunction "E10_39") (pintype "bidirectional"))
    )
    (net (code "71") (name "/E11") (class "Default")
      (node (ref "J23") (pin "6") (pinfunction "6_6") (pintype "unspecified"))
      (node (ref "R64") (pin "1") (pinfunction "1_1") (pintype "unspecified"))
      (node (ref "STM32F1DISCOVERY") (pin "15") (pinfunction "E11_15") (pintype "bidirectional"))
    )
    (net (code "72") (name "/E12") (class "Default")
      (node (ref "J24") (pin "2") (pinfunction "2_2") (pintype "unspecified"))
      (node (ref "R55") (pin "1") (pinfunction "1_1") (pintype "unspecified"))
      (node (ref "STM32F1DISCOVERY") (pin "40") (pinfunction "E12_40") (pintype "bidirectional"))
    )
    (net (code "73") (name "/E13") (class "Default")
      (node (ref "J22") (pin "6") (pinfunction "6_6") (pintype "unspecified"))
      (node (ref "R65") (pin "1") (pinfunction "1_1") (pintype "unspecified"))
      (node (ref "STM32F1DISCOVERY") (pin "16") (pinfunction "E13_16") (pintype "bidirectional"))
    )
    (net (code "74") (name "/E14") (class "Default")
      (node (ref "J24") (pin "6") (pinfunction "6_6") (pintype "unspecified"))
      (node (ref "R66") (pin "1") (pinfunction "1_1") (pintype "unspecified"))
      (node (ref "STM32F1DISCOVERY") (pin "41") (pinfunction "E14_41") (pintype "bidirectional"))
    )
    (net (code "75") (name "/E15") (class "Default")
      (node (ref "STM32F1DISCOVERY") (pin "17") (pinfunction "E15_17") (pintype "bidirectional"))
    )
    (net (code "76") (name "GND") (class "Default")
      (node (ref "H1") (pin "8") (pinfunction "8_8") (pintype "unspecified"))
      (node (ref "H2") (pin "8") (pinfunction "8_8") (pintype "unspecified"))
      (node (ref "H3") (pin "8") (pinfunction "8_8") (pintype "unspecified"))
      (node (ref "H4") (pin "8") (pinfunction "8_8") (pintype "unspecified"))
      (node (ref "H6") (pin "2") (pinfunction "2_2") (pintype "unspecified"))
      (node (ref "H7") (pin "8") (pinfunction "8_8") (pintype "unspecified"))
      (node (ref "J1") (pin "4") (pinfunction "4_4") (pintype "unspecified"))
      (node (ref "J10") (pin "1") (pinfunction "1_1") (pintype "input"))
      (node (ref "J11") (pin "1") (pinfunction "1_1") (pintype "input"))
      (node (ref "J12") (pin "1") (pinfunction "1_1") (pintype "input"))
      (node (ref "J13") (pin "2") (pinfunction "2_2") (pintype "unspecified"))
      (node (ref "J14") (pin "2") (pinfunction "2_2") (pintype "unspecified"))
      (node (ref "J15") (pin "2") (pinfunction "2_2") (pintype "unspecified"))
      (node (ref "J16") (pin "2") (pinfunction "2_2") (pintype "unspecified"))
      (node (ref "J17") (pin "10") (pinfunction "10_10") (pintype "unspecified"))
      (node (ref "J18") (pin "10") (pinfunction "10_10") (pintype "unspecified"))
      (node (ref "J19") (pin "10") (pinfunction "10_10") (pintype "unspecified"))
      (node (ref "J2") (pin "3") (pinfunction "3_3") (pintype "input"))
      (node (ref "J20") (pin "10") (pinfunction "10_10") (pintype "unspecified"))
      (node (ref "J21") (pin "10") (pinfunction "10_10") (pintype "unspecified"))
      (node (ref "J22") (pin "10") (pinfunction "10_10") (pintype "unspecified"))
      (node (ref "J23") (pin "10") (pinfunction "10_10") (pintype "unspecified"))
      (node (ref "J24") (pin "10") (pinfunction "10_10") (pintype "unspecified"))
      (node (ref "J25") (pin "2") (pinfunction "2_2") (pintype "unspecified"))
      (node (ref "J26") (pin "4") (pinfunction "4_4") (pintype "unspecified"))
      (node (ref "J27") (pin "1") (pinfunction "1_1") (pintype "unspecified"))
      (node (ref "J28") (pin "3") (pinfunction "3_3") (pintype "input"))
      (node (ref "J29") (pin "3") (pinfunction "3_3") (pintype "input"))
      (node (ref "J3") (pin "4") (pinfunction "4_4") (pintype "unspecified"))
      (node (ref "J30") (pin "4") (pinfunction "4_4") (pintype "unspecified"))
      (node (ref "J4") (pin "4") (pinfunction "4_4") (pintype "unspecified"))
      (node (ref "J5") (pin "4") (pinfunction "4_4") (pintype "unspecified"))
      (node (ref "J6") (pin "4") (pinfunction "4_4") (pintype "unspecified"))
      (node (ref "J7") (pin "1") (pinfunction "1_1") (pintype "input"))
      (node (ref "J8") (pin "1") (pinfunction "1_1") (pintype "input"))
      (node (ref "J9") (pin "1") (pinfunction "1_1") (pintype "input"))
      (node (ref "STM32F1DISCOVERY") (pin "1") (pinfunction "GND_1") (pintype "passive"))
      (node (ref "STM32F1DISCOVERY") (pin "100") (pinfunction "GND_100") (pintype "passive"))
      (node (ref "STM32F1DISCOVERY") (pin "12") (pinfunction "GND_12") (pintype "passive"))
      (node (ref "STM32F1DISCOVERY") (pin "25") (pinfunction "GND_25") (pintype "unspecified"))
      (node (ref "STM32F1DISCOVERY") (pin "26") (pinfunction "GND_26") (pintype "passive"))
      (node (ref "STM32F1DISCOVERY") (pin "3") (pinfunction "GND_3") (pintype "passive"))
      (node (ref "STM32F1DISCOVERY") (pin "50") (pinfunction "GND_50") (pintype "unspecified"))
      (node (ref "STM32F1DISCOVERY") (pin "51") (pinfunction "GND_51") (pintype "passive"))
      (node (ref "STM32F1DISCOVERY") (pin "75") (pinfunction "GND_75") (pintype "unspecified"))
      (node (ref "STM32F1DISCOVERY") (pin "76") (pinfunction "GND_76") (pintype "passive"))
    )
    (net (code "77") (name "unconnected-(H1-Pad5)") (class "Default")
      (node (ref "H1") (pin "5") (pinfunction "5_5") (pintype "unspecified+no_connect"))
    )
    (net (code "78") (name "unconnected-(H1-Pad6)") (class "Default")
      (node (ref "H1") (pin "6") (pinfunction "6_6") (pintype "unspecified+no_connect"))
    )
    (net (code "79") (name "unconnected-(H2-Pad5)") (class "Default")
      (node (ref "H2") (pin "5") (pinfunction "5_5") (pintype "unspecified+no_connect"))
    )
    (net (code "80") (name "unconnected-(H2-Pad6)") (class "Default")
      (node (ref "H2") (pin "6") (pinfunction "6_6") (pintype "unspecified+no_connect"))
    )
    (net (code "81") (name "unconnected-(H3-Pad5)") (class "Default")
      (node (ref "H3") (pin "5") (pinfunction "5_5") (pintype "unspecified+no_connect"))
    )
    (net (code "82") (name "unconnected-(H3-Pad6)") (class "Default")
      (node (ref "H3") (pin "6") (pinfunction "6_6") (pintype "unspecified+no_connect"))
    )
    (net (code "83") (name "unconnected-(H4-Pad5)") (class "Default")
      (node (ref "H4") (pin "5") (pinfunction "5_5") (pintype "unspecified+no_connect"))
    )
    (net (code "84") (name "unconnected-(H4-Pad6)") (class "Default")
      (node (ref "H4") (pin "6") (pinfunction "6_6") (pintype "unspecified+no_connect"))
    )
    (net (code "85") (name "unconnected-(H6-Pad7)") (class "Default")
      (node (ref "H6") (pin "7") (pinfunction "7_7") (pintype "unspecified"))
    )
    (net (code "86") (name "unconnected-(H7-Pad5)") (class "Default")
      (node (ref "H7") (pin "5") (pinfunction "5_5") (pintype "unspecified+no_connect"))
    )
    (net (code "87") (name "unconnected-(H7-Pad6)") (class "Default")
      (node (ref "H7") (pin "6") (pinfunction "6_6") (pintype "unspecified+no_connect"))
    )
    (net (code "88") (name "unconnected-(J17-Pad3)") (class "Default")
      (node (ref "J17") (pin "3") (pinfunction "3_3") (pintype "unspecified"))
    )
    (net (code "89") (name "unconnected-(J17-Pad4)") (class "Default")
      (node (ref "J17") (pin "4") (pinfunction "4_4") (pintype "unspecified"))
    )
    (net (code "90") (name "unconnected-(J17-Pad5)") (class "Default")
      (node (ref "J17") (pin "5") (pinfunction "5_5") (pintype "unspecified"))
    )
    (net (code "91") (name "unconnected-(J17-Pad7)") (class "Default")
      (node (ref "J17") (pin "7") (pinfunction "7_7") (pintype "unspecified"))
    )
    (net (code "92") (name "unconnected-(J17-Pad8)") (class "Default")
      (node (ref "J17") (pin "8") (pinfunction "8_8") (pintype "unspecified"))
    )
    (net (code "93") (name "unconnected-(J18-Pad3)") (class "Default")
      (node (ref "J18") (pin "3") (pinfunction "3_3") (pintype "unspecified"))
    )
    (net (code "94") (name "unconnected-(J18-Pad4)") (class "Default")
      (node (ref "J18") (pin "4") (pinfunction "4_4") (pintype "unspecified"))
    )
    (net (code "95") (name "unconnected-(J18-Pad5)") (class "Default")
      (node (ref "J18") (pin "5") (pinfunction "5_5") (pintype "unspecified"))
    )
    (net (code "96") (name "unconnected-(J18-Pad7)") (class "Default")
      (node (ref "J18") (pin "7") (pinfunction "7_7") (pintype "unspecified"))
    )
    (net (code "97") (name "unconnected-(J18-Pad8)") (class "Default")
      (node (ref "J18") (pin "8") (pinfunction "8_8") (pintype "unspecified"))
    )
    (net (code "98") (name "unconnected-(J19-Pad3)") (class "Default")
      (node (ref "J19") (pin "3") (pinfunction "3_3") (pintype "unspecified"))
    )
    (net (code "99") (name "unconnected-(J19-Pad4)") (class "Default")
      (node (ref "J19") (pin "4") (pinfunction "4_4") (pintype "unspecified"))
    )
    (net (code "100") (name "unconnected-(J19-Pad5)") (class "Default")
      (node (ref "J19") (pin "5") (pinfunction "5_5") (pintype "unspecified"))
    )
    (net (code "101") (name "unconnected-(J19-Pad7)") (class "Default")
      (node (ref "J19") (pin "7") (pinfunction "7_7") (pintype "unspecified"))
    )
    (net (code "102") (name "unconnected-(J19-Pad8)") (class "Default")
      (node (ref "J19") (pin "8") (pinfunction "8_8") (pintype "unspecified"))
    )
    (net (code "103") (name "unconnected-(J20-Pad3)") (class "Default")
      (node (ref "J20") (pin "3") (pinfunction "3_3") (pintype "unspecified"))
    )
    (net (code "104") (name "unconnected-(J20-Pad4)") (class "Default")
      (node (ref "J20") (pin "4") (pinfunction "4_4") (pintype "unspecified"))
    )
    (net (code "105") (name "unconnected-(J20-Pad5)") (class "Default")
      (node (ref "J20") (pin "5") (pinfunction "5_5") (pintype "unspecified"))
    )
    (net (code "106") (name "unconnected-(J20-Pad7)") (class "Default")
      (node (ref "J20") (pin "7") (pinfunction "7_7") (pintype "unspecified"))
    )
    (net (code "107") (name "unconnected-(J20-Pad8)") (class "Default")
      (node (ref "J20") (pin "8") (pinfunction "8_8") (pintype "unspecified"))
    )
    (net (code "108") (name "unconnected-(J21-Pad3)") (class "Default")
      (node (ref "J21") (pin "3") (pinfunction "3_3") (pintype "unspecified"))
    )
    (net (code "109") (name "unconnected-(J21-Pad4)") (class "Default")
      (node (ref "J21") (pin "4") (pinfunction "4_4") (pintype "unspecified"))
    )
    (net (code "110") (name "unconnected-(J21-Pad5)") (class "Default")
      (node (ref "J21") (pin "5") (pinfunction "5_5") (pintype "unspecified"))
    )
    (net (code "111") (name "unconnected-(J21-Pad7)") (class "Default")
      (node (ref "J21") (pin "7") (pinfunction "7_7") (pintype "unspecified"))
    )
    (net (code "112") (name "unconnected-(J21-Pad8)") (class "Default")
      (node (ref "J21") (pin "8") (pinfunction "8_8") (pintype "unspecified"))
    )
    (net (code "113") (name "unconnected-(J22-Pad3)") (class "Default")
      (node (ref "J22") (pin "3") (pinfunction "3_3") (pintype "unspecified"))
    )
    (net (code "114") (name "unconnected-(J22-Pad4)") (class "Default")
      (node (ref "J22") (pin "4") (pinfunction "4_4") (pintype "unspecified"))
    )
    (net (code "115") (name "unconnected-(J22-Pad5)") (class "Default")
      (node (ref "J22") (pin "5") (pinfunction "5_5") (pintype "unspecified"))
    )
    (net (code "116") (name "unconnected-(J22-Pad7)") (class "Default")
      (node (ref "J22") (pin "7") (pinfunction "7_7") (pintype "unspecified"))
    )
    (net (code "117") (name "unconnected-(J22-Pad8)") (class "Default")
      (node (ref "J22") (pin "8") (pinfunction "8_8") (pintype "unspecified"))
    )
    (net (code "118") (name "unconnected-(J23-Pad3)") (class "Default")
      (node (ref "J23") (pin "3") (pinfunction "3_3") (pintype "unspecified"))
    )
    (net (code "119") (name "unconnected-(J23-Pad4)") (class "Default")
      (node (ref "J23") (pin "4") (pinfunction "4_4") (pintype "unspecified"))
    )
    (net (code "120") (name "unconnected-(J23-Pad5)") (class "Default")
      (node (ref "J23") (pin "5") (pinfunction "5_5") (pintype "unspecified"))
    )
    (net (code "121") (name "unconnected-(J23-Pad7)") (class "Default")
      (node (ref "J23") (pin "7") (pinfunction "7_7") (pintype "unspecified"))
    )
    (net (code "122") (name "unconnected-(J23-Pad8)") (class "Default")
      (node (ref "J23") (pin "8") (pinfunction "8_8") (pintype "unspecified"))
    )
    (net (code "123") (name "unconnected-(J24-Pad3)") (class "Default")
      (node (ref "J24") (pin "3") (pinfunction "3_3") (pintype "unspecified"))
    )
    (net (code "124") (name "unconnected-(J24-Pad4)") (class "Default")
      (node (ref "J24") (pin "4") (pinfunction "4_4") (pintype "unspecified"))
    )
    (net (code "125") (name "unconnected-(J24-Pad5)") (class "Default")
      (node (ref "J24") (pin "5") (pinfunction "5_5") (pintype "unspecified"))
    )
    (net (code "126") (name "unconnected-(J24-Pad7)") (class "Default")
      (node (ref "J24") (pin "7") (pinfunction "7_7") (pintype "unspecified"))
    )
    (net (code "127") (name "unconnected-(J24-Pad8)") (class "Default")
      (node (ref "J24") (pin "8") (pinfunction "8_8") (pintype "unspecified"))
    )
    (net (code "128") (name "unconnected-(J28-Pad2)") (class "Default")
      (node (ref "J28") (pin "2") (pinfunction "2_2") (pintype "input"))
    )
    (net (code "129") (name "unconnected-(J29-Pad2)") (class "Default")
      (node (ref "J29") (pin "2") (pinfunction "2_2") (pintype "input"))
    )
    (net (code "130") (name "unconnected-(STM32F1DISCOVERY-3V3-Pad78)") (class "Default")
      (node (ref "STM32F1DISCOVERY") (pin "78") (pinfunction "3V3_78") (pintype "passive"))
    )
    (net (code "131") (name "unconnected-(STM32F1DISCOVERY-A13-Pad96)") (class "Default")
      (node (ref "STM32F1DISCOVERY") (pin "96") (pinfunction "A13_96") (pintype "bidirectional+no_connect"))
    )
    (net (code "132") (name "unconnected-(STM32F1DISCOVERY-A14-Pad70)") (class "Default")
      (node (ref "STM32F1DISCOVERY") (pin "70") (pinfunction "A14_70") (pintype "bidirectional+no_connect"))
    )
    (net (code "133") (name "unconnected-(STM32F1DISCOVERY-A15-Pad95)") (class "Default")
      (node (ref "STM32F1DISCOVERY") (pin "95") (pinfunction "A15_95") (pintype "bidirectional+no_connect"))
    )
    (net (code "134") (name "unconnected-(STM32F1DISCOVERY-BOOT0-Pad61)") (class "Default")
      (node (ref "STM32F1DISCOVERY") (pin "61") (pinfunction "BOOT0_61") (pintype "unspecified"))
    )
    (net (code "135") (name "unconnected-(STM32F1DISCOVERY-C5-Pad10)") (class "Default")
      (node (ref "STM32F1DISCOVERY") (pin "10") (pinfunction "C5_10") (pintype "bidirectional"))
    )
    (net (code "136") (name "unconnected-(STM32F1DISCOVERY-C14-Pad55)") (class "Default")
      (node (ref "STM32F1DISCOVERY") (pin "55") (pinfunction "C14_55") (pintype "bidirectional+no_connect"))
    )
    (net (code "137") (name "unconnected-(STM32F1DISCOVERY-H0-Pad54)") (class "Default")
      (node (ref "STM32F1DISCOVERY") (pin "54") (pinfunction "H0_54") (pintype "unspecified"))
    )
    (net (code "138") (name "unconnected-(STM32F1DISCOVERY-H1-Pad79)") (class "Default")
      (node (ref "STM32F1DISCOVERY") (pin "79") (pinfunction "H1_79") (pintype "unspecified"))
    )
    (net (code "139") (name "unconnected-(STM32F1DISCOVERY-NC-Pad49)") (class "Default")
      (node (ref "STM32F1DISCOVERY") (pin "49") (pinfunction "NC_49") (pintype "unspecified"))
    )
    (net (code "140") (name "unconnected-(STM32F1DISCOVERY-NRST-Pad28)") (class "Default")
      (node (ref "STM32F1DISCOVERY") (pin "28") (pinfunction "NRST_28") (pintype "unspecified"))
    )
    (net (code "141") (name "unconnected-(STM32F1DISCOVERY-VDD-Pad2)") (class "Default")
      (node (ref "STM32F1DISCOVERY") (pin "2") (pinfunction "VDD_2") (pintype "passive"))
    )
    (net (code "142") (name "unconnected-(STM32F1DISCOVERY-VDD-Pad27)") (class "Default")
      (node (ref "STM32F1DISCOVERY") (pin "27") (pinfunction "VDD_27") (pintype "unspecified"))
    )
    (net (code "143") (name "unconnected-(STM32F1DISCOVERY-VDD-Pad86)") (class "Default")
      (node (ref "STM32F1DISCOVERY") (pin "86") (pinfunction "VDD_86") (pintype "passive"))
    )
  )
)
